# Condor2a_ESC.net
KiCad netlist of a schematic drawn in Altium Designer
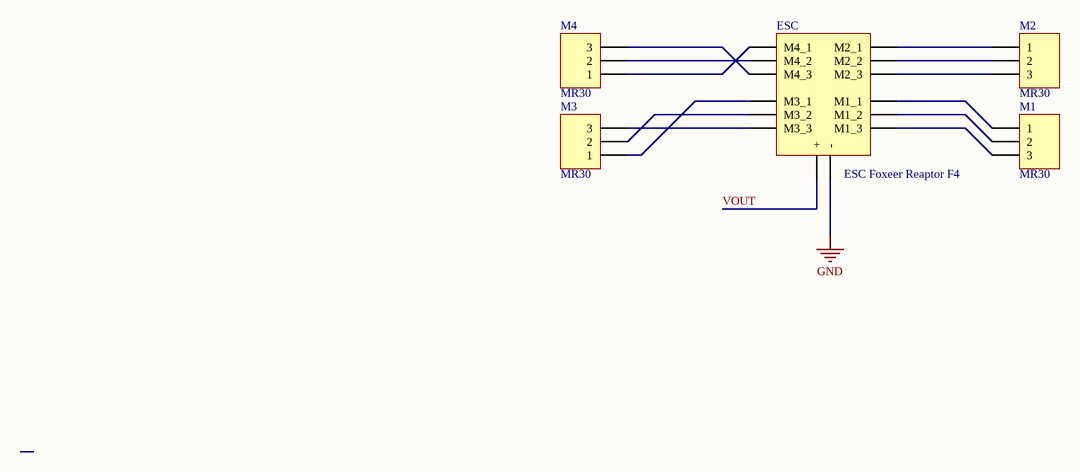
[diagram p0: Condor2a_ESC.SchDoc]

(export (version "E")
  (design (tool "Eeschema 10.0.6"))
  (components
    (comp (ref "ESC")
      (value "ESC Foxeer Reaptor F4")
      (footprint "FOXEeR REAPER")
      (libsource (lib "CB_REV_C") (part "ESC Foxeer Reaptor F4"))
    )
    (comp (ref "M1")
      (value "MR30")
      (footprint "MR30")
      (fields (field (name "PUBLISHER") "Altium Limited"))
      (libsource (lib "CB_REV_C") (part "MR30"))
    )
    (comp (ref "M2")
      (value "MR30")
      (footprint "MR30")
      (fields (field (name "PUBLISHER") "Altium Limited"))
      (libsource (lib "CB_REV_C") (part "MR30"))
    )
    (comp (ref "M3")
      (value "MR30")
      (footprint "MR30")
      (fields (field (name "PUBLISHER") "Altium Limited"))
      (libsource (lib "") (part "MR30_1"))
    )
    (comp (ref "M4")
      (value "MR30")
      (footprint "MR30")
      (fields (field (name "PUBLISHER") "Altium Limited"))
      (libsource (lib "") (part "MR30_1"))
    )
  )
  (nets
    (net (code "2") (name "/VOUT") (class "Default")
      (node (ref "ESC") (pin "7") (pinfunction "+_7") (pintype "passive"))
    )
    (net (code "3") (name "GND") (class "Default")
      (node (ref "ESC") (pin "8") (pinfunction "-_8") (pintype "passive"))
    )
    (net (code "4") (name "Net-(ESC-M1_1)") (class "Default")
      (node (ref "ESC") (pin "11") (pinfunction "M1_1_11") (pintype "passive"))
      (node (ref "M1") (pin "1") (pinfunction "1_1") (pintype "passive"))
    )
    (net (code "5") (name "Net-(ESC-M1_2)") (class "Default")
      (node (ref "ESC") (pin "10") (pinfunction "M1_2_10") (pintype "passive"))
      (node (ref "M1") (pin "2") (pinfunction "2_2") (pintype "passive"))
    )
    (net (code "6") (name "Net-(ESC-M1_3)") (class "Default")
      (node (ref "ESC") (pin "9") (pinfunction "M1_3_9") (pintype "passive"))
      (node (ref "M1") (pin "3") (pinfunction "3_3") (pintype "passive"))
    )
    (net (code "7") (name "Net-(ESC-M2_1)") (class "Default")
      (node (ref "ESC") (pin "14") (pinfunction "M2_1_14") (pintype "passive"))
      (node (ref "M2") (pin "1") (pinfunction "1_1") (pintype "passive"))
    )
    (net (code "8") (name "Net-(ESC-M2_2)") (class "Default")
      (node (ref "ESC") (pin "13") (pinfunction "M2_2_13") (pintype "passive"))
      (node (ref "M2") (pin "2") (pinfunction "2_2") (pintype "passive"))
    )
    (net (code "9") (name "Net-(ESC-M2_3)") (class "Default")
      (node (ref "ESC") (pin "12") (pinfunction "M2_3_12") (pintype "passive"))
      (node (ref "M2") (pin "3") (pinfunction "3_3") (pintype "passive"))
    )
    (net (code "10") (name "Net-(ESC-M3_1)") (class "Default")
      (node (ref "ESC") (pin "4") (pinfunction "M3_1_4") (pintype "passive"))
      (node (ref "M3") (pin "1") (pinfunction "1_1") (pintype "passive"))
    )
    (net (code "11") (name "Net-(ESC-M3_2)") (class "Default")
      (node (ref "ESC") (pin "5") (pinfunction "M3_2_5") (pintype "passive"))
      (node (ref "M3") (pin "2") (pinfunction "2_2") (pintype "passive"))
    )
    (net (code "12") (name "Net-(ESC-M3_3)") (class "Default")
      (node (ref "ESC") (pin "6") (pinfunction "M3_3_6") (pintype "passive"))
      (node (ref "M3") (pin "3") (pinfunction "3_3") (pintype "passive"))
    )
    (net (code "13") (name "Net-(ESC-M4_1)") (class "Default")
      (node (ref "ESC") (pin "1") (pinfunction "M4_1_1") (pintype "passive"))
      (node (ref "M4") (pin "1") (pinfunction "1_1") (pintype "passive"))
    )
    (net (code "14") (name "Net-(ESC-M4_2)") (class "Default")
      (node (ref "ESC") (pin "2") (pinfunction "M4_2_2") (pintype "passive"))
      (node (ref "M4") (pin "2") (pinfunction "2_2") (pintype "passive"))
    )
    (net (code "15") (name "Net-(ESC-M4_3)") (class "Default")
      (node (ref "ESC") (pin "3") (pinfunction "M4_3_3") (pintype "passive"))
      (node (ref "M4") (pin "3") (pinfunction "3_3") (pintype "passive"))
    )
  )
)
